# PSU.net
KiCad netlist of a schematic drawn in Altium Designer
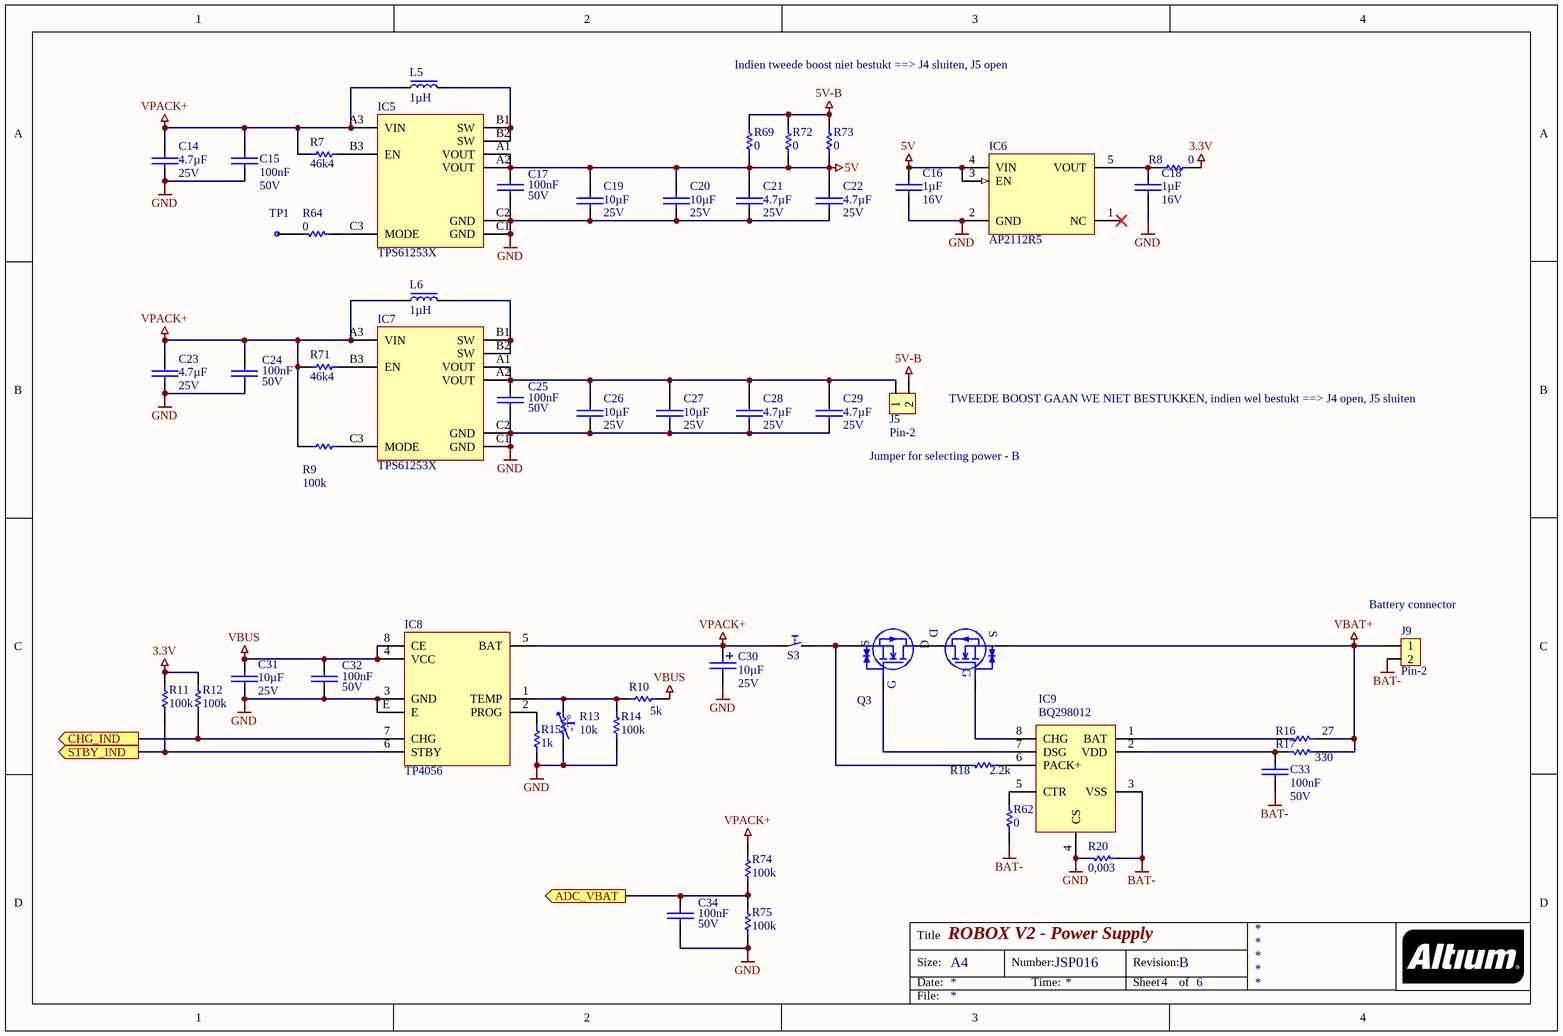
[diagram p0: PSU.SchDoc]

(export (version "E")
  (design (tool "Eeschema 10.0.6"))
  (components
    (comp (ref "C14")
      (value "4.7µF")
      (footprint "C0805")
      (description "CAP CER 4.7UF 25V X5R 0805")
      (fields
        (field (name "MANUFACTURER") "Samsung Electro-Mechanics")
        (field (name "TOLERANCE") "10%")
        (field (name "VOLTAGE") "25V")
      )
      (libsource (lib "bond-altium-excell") (part "cap_non_pol"))
    )
    (comp (ref "C15")
      (value "100nF")
      (footprint "C0402")
      (description "CAP CER 0.1UF 50V X5R 0402")
      (fields
        (field (name "MANUFACTURER") "Murata Electronics")
        (field (name "TOLERANCE") "5%")
        (field (name "VOLTAGE") "50V")
      )
      (libsource (lib "bond-altium-excell") (part "cap_non_pol"))
    )
    (comp (ref "C16")
      (value "1µF")
      (footprint "C0402")
      (description "CAP CER 1UF 16V X5R 0402")
      (fields
        (field (name "MANUFACTURER") "Samsung Electro-Mechanics")
        (field (name "TOLERANCE") "10%")
        (field (name "VOLTAGE") "16V")
      )
      (libsource (lib "bond-altium-excell") (part "cap_non_pol"))
    )
    (comp (ref "C17")
      (value "100nF")
      (footprint "C0402")
      (description "CAP CER 0.1UF 50V X5R 0402")
      (fields
        (field (name "MANUFACTURER") "Murata Electronics")
        (field (name "TOLERANCE") "5%")
        (field (name "VOLTAGE") "50V")
      )
      (libsource (lib "bond-altium-excell") (part "cap_non_pol"))
    )
    (comp (ref "C18")
      (value "1µF")
      (footprint "C0402")
      (description "CAP CER 1UF 16V X5R 0402")
      (fields
        (field (name "MANUFACTURER") "Samsung Electro-Mechanics")
        (field (name "TOLERANCE") "10%")
        (field (name "VOLTAGE") "16V")
      )
      (libsource (lib "bond-altium-excell") (part "cap_non_pol"))
    )
    (comp (ref "C19")
      (value "10µF")
      (footprint "C0603")
      (description "CAP CER 10UF 25V X5R 10% SMD")
      (fields
        (field (name "MANUFACTURER") "Murata Electronics")
        (field (name "TOLERANCE") "10%")
        (field (name "VOLTAGE") "25V")
      )
      (libsource (lib "bond-altium-excell") (part "cap_non_pol"))
    )
    (comp (ref "C20")
      (value "10µF")
      (footprint "C0603")
      (description "CAP CER 10UF 25V X5R 10% SMD")
      (fields
        (field (name "MANUFACTURER") "Murata Electronics")
        (field (name "TOLERANCE") "10%")
        (field (name "VOLTAGE") "25V")
      )
      (libsource (lib "bond-altium-excell") (part "cap_non_pol"))
    )
    (comp (ref "C21")
      (value "4.7µF")
      (footprint "C0805")
      (description "CAP CER 4.7UF 25V X5R 0805")
      (fields
        (field (name "MANUFACTURER") "Samsung Electro-Mechanics")
        (field (name "TOLERANCE") "10%")
        (field (name "VOLTAGE") "25V")
      )
      (libsource (lib "bond-altium-excell") (part "cap_non_pol"))
    )
    (comp (ref "C22")
      (value "4.7µF")
      (footprint "C0805")
      (description "CAP CER 4.7UF 25V X5R 0805")
      (fields
        (field (name "MANUFACTURER") "Samsung Electro-Mechanics")
        (field (name "TOLERANCE") "10%")
        (field (name "VOLTAGE") "25V")
      )
      (libsource (lib "bond-altium-excell") (part "cap_non_pol"))
    )
    (comp (ref "C23")
      (value "4.7µF")
      (footprint "C0805")
      (description "CAP CER 4.7UF 25V X5R 0805")
      (fields
        (field (name "MANUFACTURER") "Samsung Electro-Mechanics")
        (field (name "TOLERANCE") "10%")
        (field (name "VOLTAGE") "25V")
      )
      (libsource (lib "bond-altium-excell") (part "cap_non_pol"))
    )
    (comp (ref "C24")
      (value "100nF")
      (footprint "C0402")
      (description "CAP CER 0.1UF 50V X5R 0402")
      (fields
        (field (name "MANUFACTURER") "Murata Electronics")
        (field (name "TOLERANCE") "5%")
        (field (name "VOLTAGE") "50V")
      )
      (libsource (lib "bond-altium-excell") (part "cap_non_pol"))
    )
    (comp (ref "C25")
      (value "100nF")
      (footprint "C0402")
      (description "CAP CER 0.1UF 50V X5R 0402")
      (fields
        (field (name "MANUFACTURER") "Murata Electronics")
        (field (name "TOLERANCE") "5%")
        (field (name "VOLTAGE") "50V")
      )
      (libsource (lib "bond-altium-excell") (part "cap_non_pol"))
    )
    (comp (ref "C26")
      (value "10µF")
      (footprint "C0603")
      (description "CAP CER 10UF 25V X5R 10% SMD")
      (fields
        (field (name "MANUFACTURER") "Murata Electronics")
        (field (name "TOLERANCE") "10%")
        (field (name "VOLTAGE") "25V")
      )
      (libsource (lib "bond-altium-excell") (part "cap_non_pol"))
    )
    (comp (ref "C27")
      (value "10µF")
      (footprint "C0603")
      (description "CAP CER 10UF 25V X5R 10% SMD")
      (fields
        (field (name "MANUFACTURER") "Murata Electronics")
        (field (name "TOLERANCE") "10%")
        (field (name "VOLTAGE") "25V")
      )
      (libsource (lib "bond-altium-excell") (part "cap_non_pol"))
    )
    (comp (ref "C28")
      (value "4.7µF")
      (footprint "C0805")
      (description "CAP CER 4.7UF 25V X5R 0805")
      (fields
        (field (name "MANUFACTURER") "Samsung Electro-Mechanics")
        (field (name "TOLERANCE") "10%")
        (field (name "VOLTAGE") "25V")
      )
      (libsource (lib "bond-altium-excell") (part "cap_non_pol"))
    )
    (comp (ref "C29")
      (value "4.7µF")
      (footprint "C0805")
      (description "CAP CER 4.7UF 25V X5R 0805")
      (fields
        (field (name "MANUFACTURER") "Samsung Electro-Mechanics")
        (field (name "TOLERANCE") "10%")
        (field (name "VOLTAGE") "25V")
      )
      (libsource (lib "bond-altium-excell") (part "cap_non_pol"))
    )
    (comp (ref "C30")
      (value "10µF")
      (footprint "CD6.3H12TH")
      (description "CAP ALUM 10UF 20% 25V TH")
      (fields
        (field (name "MANUFACTURER") "Yunxing")
        (field (name "TOLERANCE") "20%")
        (field (name "VOLTAGE") "25V")
      )
      (libsource (lib "bond-altium-excell") (part "cap-pol"))
    )
    (comp (ref "C31")
      (value "10µF")
      (footprint "C0603")
      (description "CAP CER 10UF 25V X5R 10% SMD")
      (fields
        (field (name "MANUFACTURER") "Murata Electronics")
        (field (name "TOLERANCE") "10%")
        (field (name "VOLTAGE") "25V")
      )
      (libsource (lib "bond-altium-excell") (part "cap_non_pol"))
    )
    (comp (ref "C32")
      (value "100nF")
      (footprint "C0402")
      (description "CAP CER 0.1UF 50V X5R 0402")
      (fields
        (field (name "MANUFACTURER") "Murata Electronics")
        (field (name "TOLERANCE") "5%")
        (field (name "VOLTAGE") "50V")
      )
      (libsource (lib "bond-altium-excell") (part "cap_non_pol"))
    )
    (comp (ref "C33")
      (value "100nF")
      (footprint "TH5.08")
      (description "CAP CER TH 100nF X7R 50V")
      (fields
        (field (name "MANUFACTURER") "FH")
        (field (name "TOLERANCE") "10%")
        (field (name "VOLTAGE") "50V")
      )
      (libsource (lib "bond-altium-excell") (part "cap_non_pol"))
    )
    (comp (ref "C34")
      (value "100nF")
      (footprint "C0402")
      (description "CAP CER 0.1UF 50V X5R 0402")
      (fields
        (field (name "MANUFACTURER") "Murata Electronics")
        (field (name "TOLERANCE") "5%")
        (field (name "VOLTAGE") "50V")
      )
      (libsource (lib "bond-altium-excell") (part "cap_non_pol"))
    )
    (comp (ref "IC5")
      (value "TPS61253X")
      (footprint "DSBGA-9")
      (description "3.8-MHZ, 5.25-V / 4-A BOOST CONV")
      (fields (field (name "MANUFACTURER") "Texas Instruments"))
      (libsource (lib "bond-altium-excell") (part "TPS61253X"))
    )
    (comp (ref "IC6")
      (value "AP2112R5")
      (footprint "SOT-89-5")
      (description "IC REG LINEAR 3.3V 600MA SOT89-5")
      (fields (field (name "MANUFACTURER") "Diodes Incorporated"))
      (libsource (lib "bond-altium-excell") (part "AP2112R5"))
    )
    (comp (ref "IC7")
      (value "TPS61253X")
      (footprint "DSBGA-9")
      (description "3.8-MHZ, 5.25-V / 4-A BOOST CONV")
      (fields (field (name "MANUFACTURER") "Texas Instruments"))
      (libsource (lib "bond-altium-excell") (part "TPS61253X"))
    )
    (comp (ref "IC8")
      (value "TP4056")
      (footprint "SOIC-8-E")
      (description "IC ESOP-8 Battery Charger Management")
      (fields (field (name "MANUFACTURER") "TOPPOWER"))
      (libsource (lib "bond-altium-excell") (part "TP4056"))
    )
    (comp (ref "IC9")
      (value "BQ298012")
      (footprint "XFQFN-8")
      (description "IC BATT MON LI-ION 1CELL 8X2QFN")
      (fields (field (name "MANUFACTURER") "Texas Instruments"))
      (libsource (lib "bond-altium-excell") (part "BQ298009"))
    )
    (comp (ref "J5")
      (value "Pin-2")
      (footprint "2-PIN-EMPTY")
      (description "CONN TH solder pad")
      (libsource (lib "bond-altium-excell") (part "Pin-2"))
    )
    (comp (ref "J9")
      (value "Pin-2")
      (footprint "B075TZF7NN")
      (description "CONN BAT 18650")
      (fields (field (name "MANUFACTURER") "KEESIN"))
      (libsource (lib "") (part "Pin-2_1"))
    )
    (comp (ref "L5")
      (value "1µH")
      (footprint "L4.2X4.2X2")
      (description "FIXED IND 1UH 5.8A 26 MOHM SMD")
      (fields (field (name "MANUFACTURER") "Pulse Electronics") (field (name "TOLERANCE") "20%"))
      (libsource (lib "bond-altium-excell") (part "inductor_1"))
    )
    (comp (ref "L6")
      (value "1µH")
      (footprint "L4.2X4.2X2")
      (description "FIXED IND 1UH 5.8A 26 MOHM SMD")
      (fields (field (name "MANUFACTURER") "Pulse Electronics") (field (name "TOLERANCE") "20%"))
      (libsource (lib "bond-altium-excell") (part "inductor_1"))
    )
    (comp (ref "Q3")
      (value "N_CH_MOSFET2_DUAL")
      (footprint "CSP-6")
      (description "MOSFET 2N-CH 6CSP")
      (fields (field (name "MANUFACTURER") "onsemi"))
      (libsource (lib "bond-altium-excell") (part "N_CH_MOSFET2_DUAL"))
    )
    (comp (ref "R7")
      (value "46k4")
      (footprint "R0402")
      (description "RES SMD 46.4K OHM 1% 1/16W 0402")
      (fields (field (name "MANUFACTURER") "Yageo") (field (name "TOLERANCE") "1%"))
      (libsource (lib "bond-altium-excell") (part "resistor"))
    )
    (comp (ref "R8")
      (value "0")
      (footprint "R0402")
      (description "RES SMD 0 OHM JUMPER 1/10W 0402")
      (fields (field (name "MANUFACTURER") "Panasonic Electronic Components") (field (name "TOLERANCE") "1%"))
      (libsource (lib "bond-altium-excell") (part "resistor"))
    )
    (comp (ref "R9")
      (value "100k")
      (footprint "R0402")
      (description "RES SMD 100K OHM 1% 1/10W 0402")
      (fields (field (name "MANUFACTURER") "Panasonic Electronic Components") (field (name "TOLERANCE") "1%"))
      (libsource (lib "bond-altium-excell") (part "resistor"))
    )
    (comp (ref "R10")
      (value "5k")
      (footprint "R0402")
      (description "RES SMD 5K OHM 1% 1/16W 0402")
      (fields (field (name "MANUFACTURER") "Yageo") (field (name "TOLERANCE") "1%"))
      (libsource (lib "bond-altium-excell") (part "resistor"))
    )
    (comp (ref "R11")
      (value "100k")
      (footprint "TH6.3")
      (description "RES TH 100k OHM 5% 1/4W")
      (fields (field (name "MANUFACTURER") "VO") (field (name "TOLERANCE") "5%"))
      (libsource (lib "bond-altium-excell") (part "resistor"))
    )
    (comp (ref "R12")
      (value "100k")
      (footprint "TH6.3")
      (description "RES TH 100k OHM 5% 1/4W")
      (fields (field (name "MANUFACTURER") "VO") (field (name "TOLERANCE") "5%"))
      (libsource (lib "bond-altium-excell") (part "resistor"))
    )
    (comp (ref "R13")
      (value "10k")
      (footprint "R0402")
      (description "THERMISTOR NTC 10KOHM 3380K 0402")
      (fields (field (name "MANUFACTURER") "Murata Electronics") (field (name "TOLERANCE") "1%"))
      (libsource (lib "bond-altium-excell") (part "thermistor"))
    )
    (comp (ref "R14")
      (value "100k")
      (footprint "R0402")
      (description "RES SMD 100K OHM 1% 1/10W 0402")
      (fields (field (name "MANUFACTURER") "Panasonic Electronic Components") (field (name "TOLERANCE") "1%"))
      (libsource (lib "bond-altium-excell") (part "resistor"))
    )
    (comp (ref "R15")
      (value "1k")
      (footprint "R0402")
      (description "RES SMD 1K OHM 1% 1/10W 0402")
      (fields (field (name "MANUFACTURER") "Panasonic Electronic Components") (field (name "TOLERANCE") "1%"))
      (libsource (lib "bond-altium-excell") (part "resistor"))
    )
    (comp (ref "R16")
      (value "27")
      (footprint "R0402")
      (description "CRGCQ 0402 27R 1%")
      (fields (field (name "MANUFACTURER") "TE Connectivity Passive Product") (field (name "TOLERANCE") "1%"))
      (libsource (lib "bond-altium-excell") (part "resistor"))
    )
    (comp (ref "R17")
      (value "330")
      (footprint "R0402")
      (description "RES SMD 330 OHM 1% 1/10W 0402")
      (fields (field (name "MANUFACTURER") "Panasonic Electronic Components") (field (name "TOLERANCE") "1%"))
      (libsource (lib "bond-altium-excell") (part "resistor"))
    )
    (comp (ref "R18")
      (value "2.2k")
      (footprint "R0402")
      (description "RES 2.2K OHM 5% 1/16W 0402")
      (fields (field (name "MANUFACTURER") "Stackpole Electronics Inc") (field (name "TOLERANCE") "5%"))
      (libsource (lib "bond-altium-excell") (part "resistor"))
    )
    (comp (ref "R20")
      (value "0,003")
      (footprint "R2010")
      (description "RES 0.003 OHM 1% 1.5W 2010")
      (fields (field (name "MANUFACTURER") "Stackpole Electronics Inc") (field (name "TOLERANCE") "1%"))
      (libsource (lib "bond-altium-excell") (part "resistor"))
    )
    (comp (ref "R62")
      (value "0")
      (footprint "R0402")
      (description "RES SMD 0 OHM JUMPER 1/10W 0402")
      (fields (field (name "MANUFACTURER") "Panasonic Electronic Components") (field (name "TOLERANCE") "1%"))
      (libsource (lib "bond-altium-excell") (part "resistor"))
    )
    (comp (ref "R64")
      (value "0")
      (footprint "R0402")
      (description "RES SMD 0 OHM JUMPER 1/10W 0402")
      (fields (field (name "MANUFACTURER") "Panasonic Electronic Components") (field (name "TOLERANCE") "1%"))
      (libsource (lib "bond-altium-excell") (part "resistor"))
    )
    (comp (ref "R69")
      (value "0")
      (footprint "R0402")
      (description "RES SMD 0 OHM JUMPER 1/10W 0402")
      (fields (field (name "MANUFACTURER") "Panasonic Electronic Components") (field (name "TOLERANCE") "1%"))
      (libsource (lib "bond-altium-excell") (part "resistor"))
    )
    (comp (ref "R71")
      (value "46k4")
      (footprint "R0402")
      (description "RES SMD 46.4K OHM 1% 1/16W 0402")
      (fields (field (name "MANUFACTURER") "Yageo") (field (name "TOLERANCE") "1%"))
      (libsource (lib "bond-altium-excell") (part "resistor"))
    )
    (comp (ref "R72")
      (value "0")
      (footprint "R0402")
      (description "RES SMD 0 OHM JUMPER 1/10W 0402")
      (fields (field (name "MANUFACTURER") "Panasonic Electronic Components") (field (name "TOLERANCE") "1%"))
      (libsource (lib "bond-altium-excell") (part "resistor"))
    )
    (comp (ref "R73")
      (value "0")
      (footprint "R0402")
      (description "RES SMD 0 OHM JUMPER 1/10W 0402")
      (fields (field (name "MANUFACTURER") "Panasonic Electronic Components") (field (name "TOLERANCE") "1%"))
      (libsource (lib "bond-altium-excell") (part "resistor"))
    )
    (comp (ref "R74")
      (value "100k")
      (footprint "R0402")
      (description "RES SMD 100K OHM 1% 1/10W 0402")
      (fields (field (name "MANUFACTURER") "Panasonic Electronic Components") (field (name "TOLERANCE") "1%"))
      (libsource (lib "bond-altium-excell") (part "resistor"))
    )
    (comp (ref "R75")
      (value "100k")
      (footprint "R0402")
      (description "RES SMD 100K OHM 1% 1/10W 0402")
      (fields (field (name "MANUFACTURER") "Panasonic Electronic Components") (field (name "TOLERANCE") "1%"))
      (libsource (lib "bond-altium-excell") (part "resistor"))
    )
    (comp (ref "S3")
      (value "push-button")
      (footprint "ANT11SF1CQE")
      (description "SWITCH TOGGLE SPDT 5A 120V")
      (fields (field (name "MANUFACTURER") "CIT Relay and Switch"))
      (libsource (lib "bond-altium-excell") (part "push-button"))
    )
    (comp (ref "TP1")
      (value "TP")
      (footprint "TP_0.8MM")
      (description "Test point diameter 0.6mm")
      (libsource (lib "bond-altium-excell") (part "TP"))
    )
  )
  (nets
    (net (code "1") (name "/ADC_VBAT") (class "Default")
      (node (ref "C34") (pin "2") (pinfunction "2_2") (pintype "passive"))
      (node (ref "R74") (pin "2") (pinfunction "2_2") (pintype "passive"))
      (node (ref "R75") (pin "1") (pinfunction "1_1") (pintype "passive"))
    )
    (net (code "2") (name "/CHG_IND") (class "Default")
      (node (ref "IC8") (pin "7") (pinfunction "CHG_7") (pintype "passive"))
      (node (ref "R12") (pin "2") (pinfunction "2_2") (pintype "passive"))
    )
    (net (code "3") (name "/STBY_IND") (class "Default")
      (node (ref "IC8") (pin "6") (pinfunction "STBY_6") (pintype "passive"))
      (node (ref "R11") (pin "2") (pinfunction "2_2") (pintype "passive"))
    )
    (net (code "4") (name "3.3V") (class "Default")
      (node (ref "R11") (pin "1") (pinfunction "1_1") (pintype "passive"))
      (node (ref "R12") (pin "1") (pinfunction "1_1") (pintype "passive"))
      (node (ref "R8") (pin "1") (pinfunction "1_1") (pintype "passive"))
    )
    (net (code "5") (name "5V") (class "Default")
      (node (ref "C16") (pin "1") (pinfunction "1_1") (pintype "passive"))
      (node (ref "C17") (pin "2") (pinfunction "2_2") (pintype "passive"))
      (node (ref "C19") (pin "1") (pinfunction "1_1") (pintype "passive"))
      (node (ref "C20") (pin "1") (pinfunction "1_1") (pintype "passive"))
      (node (ref "C21") (pin "1") (pinfunction "1_1") (pintype "passive"))
      (node (ref "C22") (pin "1") (pinfunction "1_1") (pintype "passive"))
      (node (ref "IC5") (pin "A1") (pinfunction "VOUT_A1") (pintype "passive"))
      (node (ref "IC5") (pin "A2") (pinfunction "VOUT_A2") (pintype "passive"))
      (node (ref "IC6") (pin "3") (pinfunction "EN_3") (pintype "input"))
      (node (ref "IC6") (pin "4") (pinfunction "VIN_4") (pintype "power_in"))
      (node (ref "R69") (pin "2") (pinfunction "2_2") (pintype "passive"))
      (node (ref "R72") (pin "2") (pinfunction "2_2") (pintype "passive"))
      (node (ref "R73") (pin "2") (pinfunction "2_2") (pintype "passive"))
    )
    (net (code "6") (name "5V-B") (class "Default")
      (node (ref "J5") (pin "2") (pinfunction "2_2") (pintype "passive"))
      (node (ref "R69") (pin "1") (pinfunction "1_1") (pintype "passive"))
      (node (ref "R72") (pin "1") (pinfunction "1_1") (pintype "passive"))
      (node (ref "R73") (pin "1") (pinfunction "1_1") (pintype "passive"))
    )
    (net (code "7") (name "BAT-") (class "Default")
      (node (ref "C33") (pin "2") (pinfunction "2_2") (pintype "passive"))
      (node (ref "IC9") (pin "3") (pinfunction "VSS_3") (pintype "passive"))
      (node (ref "J9") (pin "2") (pinfunction "2_2") (pintype "passive"))
      (node (ref "R20") (pin "2") (pinfunction "2_2") (pintype "passive"))
      (node (ref "R62") (pin "2") (pinfunction "2_2") (pintype "passive"))
    )
    (net (code "8") (name "GND") (class "Default")
      (node (ref "C14") (pin "2") (pinfunction "2_2") (pintype "passive"))
      (node (ref "C15") (pin "2") (pinfunction "2_2") (pintype "passive"))
      (node (ref "C16") (pin "2") (pinfunction "2_2") (pintype "passive"))
      (node (ref "C17") (pin "1") (pinfunction "1_1") (pintype "passive"))
      (node (ref "C18") (pin "2") (pinfunction "2_2") (pintype "passive"))
      (node (ref "C19") (pin "2") (pinfunction "2_2") (pintype "passive"))
      (node (ref "C20") (pin "2") (pinfunction "2_2") (pintype "passive"))
      (node (ref "C21") (pin "2") (pinfunction "2_2") (pintype "passive"))
      (node (ref "C22") (pin "2") (pinfunction "2_2") (pintype "passive"))
      (node (ref "C23") (pin "2") (pinfunction "2_2") (pintype "passive"))
      (node (ref "C24") (pin "1") (pinfunction "1_1") (pintype "passive"))
      (node (ref "C25") (pin "1") (pinfunction "1_1") (pintype "passive"))
      (node (ref "C26") (pin "2") (pinfunction "2_2") (pintype "passive"))
      (node (ref "C27") (pin "2") (pinfunction "2_2") (pintype "passive"))
      (node (ref "C28") (pin "2") (pinfunction "2_2") (pintype "passive"))
      (node (ref "C29") (pin "2") (pinfunction "2_2") (pintype "passive"))
      (node (ref "C30") (pin "-") (pinfunction "-_-") (pintype "passive"))
      (node (ref "C31") (pin "2") (pinfunction "2_2") (pintype "passive"))
      (node (ref "C32") (pin "1") (pinfunction "1_1") (pintype "passive"))
      (node (ref "C34") (pin "1") (pinfunction "1_1") (pintype "passive"))
      (node (ref "IC5") (pin "C1") (pinfunction "GND_C1") (pintype "passive"))
      (node (ref "IC5") (pin "C2") (pinfunction "GND_C2") (pintype "passive"))
      (node (ref "IC6") (pin "2") (pinfunction "GND_2") (pintype "passive"))
      (node (ref "IC7") (pin "C1") (pinfunction "GND_C1") (pintype "passive"))
      (node (ref "IC7") (pin "C2") (pinfunction "GND_C2") (pintype "passive"))
      (node (ref "IC8") (pin "3") (pinfunction "GND_3") (pintype "passive"))
      (node (ref "IC8") (pin "E") (pinfunction "E_E") (pintype "passive"))
      (node (ref "IC9") (pin "4") (pinfunction "CS_4") (pintype "passive"))
      (node (ref "R13") (pin "1") (pinfunction "1_1") (pintype "passive"))
      (node (ref "R14") (pin "2") (pinfunction "2_2") (pintype "passive"))
      (node (ref "R15") (pin "2") (pinfunction "2_2") (pintype "passive"))
      (node (ref "R20") (pin "1") (pinfunction "1_1") (pintype "passive"))
      (node (ref "R75") (pin "2") (pinfunction "2_2") (pintype "passive"))
    )
    (net (code "9") (name "Net-(C25-Pad2)") (class "Default")
      (node (ref "C25") (pin "2") (pinfunction "2_2") (pintype "passive"))
      (node (ref "C26") (pin "1") (pinfunction "1_1") (pintype "passive"))
      (node (ref "C27") (pin "1") (pinfunction "1_1") (pintype "passive"))
      (node (ref "C28") (pin "1") (pinfunction "1_1") (pintype "passive"))
      (node (ref "C29") (pin "1") (pinfunction "1_1") (pintype "passive"))
      (node (ref "IC7") (pin "A1") (pinfunction "VOUT_A1") (pintype "passive"))
      (node (ref "IC7") (pin "A2") (pinfunction "VOUT_A2") (pintype "passive"))
      (node (ref "J5") (pin "1") (pinfunction "1_1") (pintype "passive"))
    )
    (net (code "10") (name "Net-(IC5-EN)") (class "Default")
      (node (ref "IC5") (pin "B3") (pinfunction "EN_B3") (pintype "passive"))
      (node (ref "R7") (pin "2") (pinfunction "2_2") (pintype "passive"))
    )
    (net (code "11") (name "Net-(IC5-MODE)") (class "Default")
      (node (ref "IC5") (pin "C3") (pinfunction "MODE_C3") (pintype "passive"))
      (node (ref "R64") (pin "1") (pinfunction "1_1") (pintype "passive"))
    )
    (net (code "12") (name "Net-(IC5-SW-PadB1)") (class "Default")
      (node (ref "IC5") (pin "B1") (pinfunction "SW_B1") (pintype "passive"))
      (node (ref "IC5") (pin "B2") (pinfunction "SW_B2") (pintype "passive"))
      (node (ref "L5") (pin "2") (pinfunction "2_2") (pintype "passive"))
    )
    (net (code "13") (name "Net-(IC6-VOUT)") (class "Default")
      (node (ref "C18") (pin "1") (pinfunction "1_1") (pintype "passive"))
      (node (ref "IC6") (pin "5") (pinfunction "VOUT_5") (pintype "power_in"))
      (node (ref "R8") (pin "2") (pinfunction "2_2") (pintype "passive"))
    )
    (net (code "14") (name "Net-(IC7-EN)") (class "Default")
      (node (ref "IC7") (pin "B3") (pinfunction "EN_B3") (pintype "passive"))
      (node (ref "R71") (pin "2") (pinfunction "2_2") (pintype "passive"))
    )
    (net (code "15") (name "Net-(IC7-MODE)") (class "Default")
      (node (ref "IC7") (pin "C3") (pinfunction "MODE_C3") (pintype "passive"))
      (node (ref "R9") (pin "1") (pinfunction "1_1") (pintype "passive"))
    )
    (net (code "16") (name "Net-(IC7-SW-PadB1)") (class "Default")
      (node (ref "IC7") (pin "B1") (pinfunction "SW_B1") (pintype "passive"))
      (node (ref "IC7") (pin "B2") (pinfunction "SW_B2") (pintype "passive"))
      (node (ref "L6") (pin "2") (pinfunction "2_2") (pintype "passive"))
    )
    (net (code "17") (name "Net-(IC8-PROG)") (class "Default")
      (node (ref "IC8") (pin "2") (pinfunction "PROG_2") (pintype "passive"))
      (node (ref "R15") (pin "1") (pinfunction "1_1") (pintype "passive"))
    )
    (net (code "18") (name "Net-(IC8-TEMP)") (class "Default")
      (node (ref "IC8") (pin "1") (pinfunction "TEMP_1") (pintype "passive"))
      (node (ref "R10") (pin "1") (pinfunction "1_1") (pintype "passive"))
      (node (ref "R13") (pin "2") (pinfunction "2_2") (pintype "passive"))
      (node (ref "R14") (pin "1") (pinfunction "1_1") (pintype "passive"))
    )
    (net (code "19") (name "Net-(IC9-BAT)") (class "Default")
      (node (ref "IC9") (pin "1") (pinfunction "BAT_1") (pintype "passive"))
      (node (ref "R16") (pin "1") (pinfunction "1_1") (pintype "passive"))
    )
    (net (code "20") (name "Net-(IC9-CHG)") (class "Default")
      (node (ref "IC9") (pin "8") (pinfunction "CHG_8") (pintype "passive"))
      (node (ref "Q3") (pin "G") (pinfunction "G_G") (pintype "passive"))
    )
    (net (code "21") (name "Net-(IC9-CTR)") (class "Default")
      (node (ref "IC9") (pin "5") (pinfunction "CTR_5") (pintype "passive"))
      (node (ref "R62") (pin "1") (pinfunction "1_1") (pintype "passive"))
    )
    (net (code "22") (name "Net-(IC9-DSG)") (class "Default")
      (node (ref "IC9") (pin "7") (pinfunction "DSG_7") (pintype "passive"))
      (node (ref "Q3") (pin "G2") (pinfunction "G2_G2") (pintype "passive"))
    )
    (net (code "23") (name "Net-(IC9-PACK+)") (class "Default")
      (node (ref "IC9") (pin "6") (pinfunction "PACK+_6") (pintype "passive"))
      (node (ref "R18") (pin "2") (pinfunction "2_2") (pintype "passive"))
    )
    (net (code "24") (name "Net-(IC9-VDD)") (class "Default")
      (node (ref "C33") (pin "1") (pinfunction "1_1") (pintype "passive"))
      (node (ref "IC9") (pin "2") (pinfunction "VDD_2") (pintype "passive"))
      (node (ref "R17") (pin "1") (pinfunction "1_1") (pintype "passive"))
    )
    (net (code "25") (name "Net-(Q3-PadS2)") (class "Default")
      (node (ref "Q3") (pin "S2") (pinfunction "S2_S2") (pintype "passive"))
      (node (ref "R18") (pin "1") (pinfunction "1_1") (pintype "passive"))
      (node (ref "S3") (pin "2") (pinfunction "2_2") (pintype "passive"))
    )
    (net (code "26") (name "Net-(R64-Pad2)") (class "Default")
      (node (ref "R64") (pin "2") (pinfunction "2_2") (pintype "passive"))
      (node (ref "TP1") (pin "1") (pinfunction "1_1") (pintype "passive"))
    )
    (net (code "27") (name "VBAT+") (class "Default")
      (node (ref "J9") (pin "1") (pinfunction "1_1") (pintype "passive"))
      (node (ref "Q3") (pin "S") (pinfunction "S_S") (pintype "passive"))
      (node (ref "R16") (pin "2") (pinfunction "2_2") (pintype "passive"))
      (node (ref "R17") (pin "2") (pinfunction "2_2") (pintype "passive"))
    )
    (net (code "28") (name "VBUS") (class "Default")
      (node (ref "C31") (pin "1") (pinfunction "1_1") (pintype "passive"))
      (node (ref "C32") (pin "2") (pinfunction "2_2") (pintype "passive"))
      (node (ref "IC8") (pin "4") (pinfunction "VCC_4") (pintype "passive"))
      (node (ref "IC8") (pin "8") (pinfunction "CE_8") (pintype "passive"))
      (node (ref "R10") (pin "2") (pinfunction "2_2") (pintype "passive"))
    )
    (net (code "29") (name "VPACK+") (class "Default")
      (node (ref "C14") (pin "1") (pinfunction "1_1") (pintype "passive"))
      (node (ref "C15") (pin "1") (pinfunction "1_1") (pintype "passive"))
      (node (ref "C23") (pin "1") (pinfunction "1_1") (pintype "passive"))
      (node (ref "C24") (pin "2") (pinfunction "2_2") (pintype "passive"))
      (node (ref "C30") (pin "+") (pinfunction "+_+") (pintype "passive"))
      (node (ref "IC5") (pin "A3") (pinfunction "VIN_A3") (pintype "passive"))
      (node (ref "IC7") (pin "A3") (pinfunction "VIN_A3") (pintype "passive"))
      (node (ref "IC8") (pin "5") (pinfunction "BAT_5") (pintype "passive"))
      (node (ref "L5") (pin "1") (pinfunction "1_1") (pintype "passive"))
      (node (ref "L6") (pin "1") (pinfunction "1_1") (pintype "passive"))
      (node (ref "R7") (pin "1") (pinfunction "1_1") (pintype "passive"))
      (node (ref "R71") (pin "1") (pinfunction "1_1") (pintype "passive"))
      (node (ref "R74") (pin "1") (pinfunction "1_1") (pintype "passive"))
      (node (ref "R9") (pin "2") (pinfunction "2_2") (pintype "passive"))
      (node (ref "S3") (pin "1") (pinfunction "1_1") (pintype "passive"))
    )
    (net (code "30") (name "unconnected-(IC6-NC-Pad1)") (class "Default")
      (node (ref "IC6") (pin "1") (pinfunction "NC_1") (pintype "passive+no_connect"))
    )
  )
)
